# Thrusters_terminals_pcb.net
KiCad netlist of a schematic drawn in EAGLE
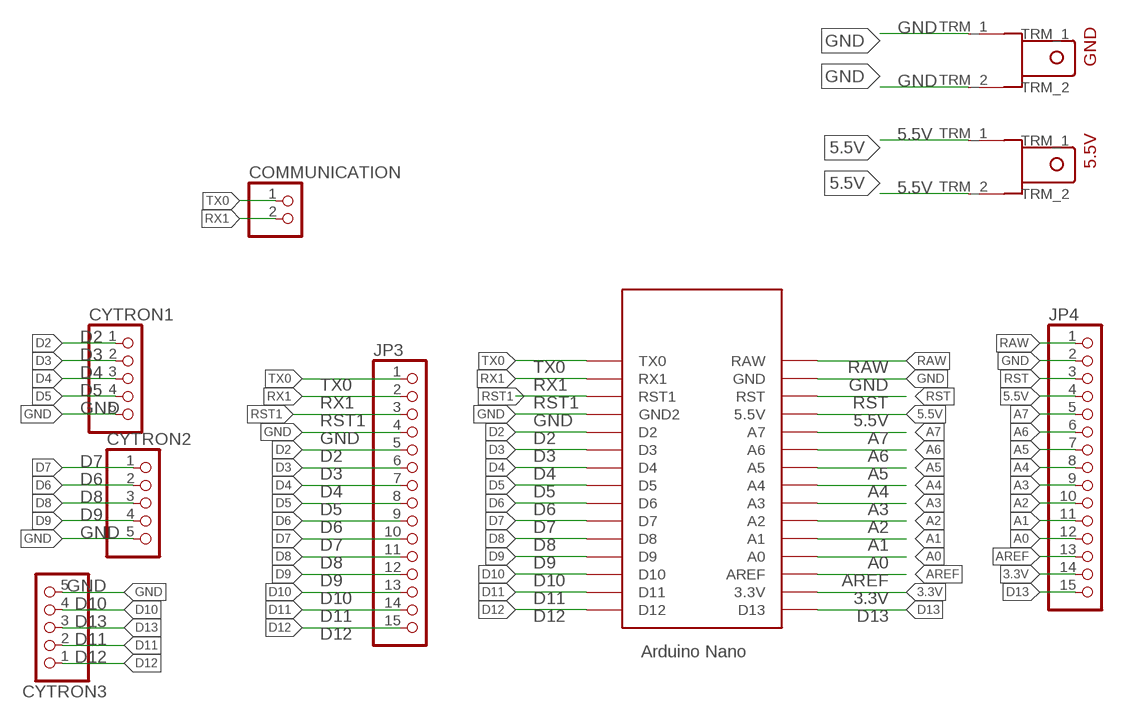
[diagram p0: schematic, sheet 1]

(export (version "E")
  (design (tool "Eeschema 10.0.6"))
  (components
    (comp (ref "5.5V")
      (value "TERMINAL_EDITED")
      (footprint "eagle-import:TERMINAL_EDITED")
      (libsource (lib "eagle-import") (part "TERMINAL_EDITED"))
    )
    (comp (ref "COMMUNICATION")
      (value "PINHD-2_DATA")
      (footprint "eagle-import:1X02_DATA")
      (libsource (lib "eagle-import") (part "PINHD-2_DATA"))
    )
    (comp (ref "CYTRON1")
      (value "PINHD-5_DATA")
      (footprint "eagle-import:1X05_DATA")
      (libsource (lib "eagle-import") (part "PINHD-5_DATA"))
    )
    (comp (ref "CYTRON2")
      (value "PINHD-5_DATA")
      (footprint "eagle-import:1X05_DATA")
      (libsource (lib "eagle-import") (part "PINHD-5_DATA"))
    )
    (comp (ref "CYTRON3")
      (value "PINHD-5_DATA")
      (footprint "eagle-import:1X05_DATA")
      (libsource (lib "eagle-import") (part "PINHD-5_DATA"))
    )
    (comp (ref "GND")
      (value "TERMINAL_EDITED")
      (footprint "eagle-import:TERMINAL_EDITED")
      (libsource (lib "eagle-import") (part "TERMINAL_EDITED"))
    )
    (comp (ref "JP3")
      (value "PINHD-1X15")
      (footprint "eagle-import:1X15")
      (libsource (lib "eagle-import") (part "PINHD-1X15"))
    )
    (comp (ref "JP4")
      (value "PINHD-1X15")
      (footprint "eagle-import:1X15")
      (libsource (lib "eagle-import") (part "PINHD-1X15"))
    )
    (comp (ref "U$1")
      (value "ARDUINO_NANO")
      (footprint "eagle-import:NANO")
      (libsource (lib "eagle-import") (part "ARDUINO_NANO"))
    )
  )
  (nets
    (net (code "1") (name "3.3V") (class "Default")
      (node (ref "JP4") (pin "14") (pinfunction "14_14") (pintype "passive"))
      (node (ref "U$1") (pin "3.3V") (pinfunction "3.3V_3.3V") (pintype "bidirectional"))
    )
    (net (code "2") (name "5.5V") (class "Default")
      (node (ref "5.5V") (pin "TRM_1") (pinfunction "TRM_1_TRM_1") (pintype "bidirectional"))
      (node (ref "5.5V") (pin "TRM_2") (pinfunction "TRM_2_TRM_2") (pintype "bidirectional"))
      (node (ref "JP4") (pin "4") (pinfunction "4_4") (pintype "passive"))
      (node (ref "U$1") (pin "5V") (pinfunction "5.5V_5V") (pintype "bidirectional"))
    )
    (net (code "3") (name "A0") (class "Default")
      (node (ref "JP4") (pin "12") (pinfunction "12_12") (pintype "passive"))
      (node (ref "U$1") (pin "A0") (pinfunction "A0_A0") (pintype "bidirectional"))
    )
    (net (code "4") (name "A1") (class "Default")
      (node (ref "JP4") (pin "11") (pinfunction "11_11") (pintype "passive"))
      (node (ref "U$1") (pin "A1") (pinfunction "A1_A1") (pintype "bidirectional"))
    )
    (net (code "5") (name "A2") (class "Default")
      (node (ref "JP4") (pin "10") (pinfunction "10_10") (pintype "passive"))
      (node (ref "U$1") (pin "A2") (pinfunction "A2_A2") (pintype "bidirectional"))
    )
    (net (code "6") (name "A3") (class "Default")
      (node (ref "JP4") (pin "9") (pinfunction "9_9") (pintype "passive"))
      (node (ref "U$1") (pin "A3") (pinfunction "A3_A3") (pintype "bidirectional"))
    )
    (net (code "7") (name "A4") (class "Default")
      (node (ref "JP4") (pin "8") (pinfunction "8_8") (pintype "passive"))
      (node (ref "U$1") (pin "A4") (pinfunction "A4_A4") (pintype "bidirectional"))
    )
    (net (code "8") (name "A5") (class "Default")
      (node (ref "JP4") (pin "7") (pinfunction "7_7") (pintype "passive"))
      (node (ref "U$1") (pin "A5") (pinfunction "A5_A5") (pintype "bidirectional"))
    )
    (net (code "9") (name "A6") (class "Default")
      (node (ref "JP4") (pin "6") (pinfunction "6_6") (pintype "passive"))
      (node (ref "U$1") (pin "A6") (pinfunction "A6_A6") (pintype "bidirectional"))
    )
    (net (code "10") (name "A7") (class "Default")
      (node (ref "JP4") (pin "5") (pinfunction "5_5") (pintype "passive"))
      (node (ref "U$1") (pin "A7") (pinfunction "A7_A7") (pintype "bidirectional"))
    )
    (net (code "11") (name "AREF") (class "Default")
      (node (ref "JP4") (pin "13") (pinfunction "13_13") (pintype "passive"))
      (node (ref "U$1") (pin "AREF") (pinfunction "AREF_AREF") (pintype "bidirectional"))
    )
    (net (code "12") (name "D2") (class "Default")
      (node (ref "CYTRON1") (pin "1") (pinfunction "1_1") (pintype "passive"))
      (node (ref "JP3") (pin "5") (pinfunction "5_5") (pintype "passive"))
      (node (ref "U$1") (pin "D2") (pinfunction "D2_D2") (pintype "bidirectional"))
    )
    (net (code "13") (name "D3") (class "Default")
      (node (ref "CYTRON1") (pin "2") (pinfunction "2_2") (pintype "passive"))
      (node (ref "JP3") (pin "6") (pinfunction "6_6") (pintype "passive"))
      (node (ref "U$1") (pin "D3") (pinfunction "D3_D3") (pintype "bidirectional"))
    )
    (net (code "14") (name "D4") (class "Default")
      (node (ref "CYTRON1") (pin "3") (pinfunction "3_3") (pintype "passive"))
      (node (ref "JP3") (pin "7") (pinfunction "7_7") (pintype "passive"))
      (node (ref "U$1") (pin "D4") (pinfunction "D4_D4") (pintype "bidirectional"))
    )
    (net (code "15") (name "D5") (class "Default")
      (node (ref "CYTRON1") (pin "4") (pinfunction "4_4") (pintype "passive"))
      (node (ref "JP3") (pin "8") (pinfunction "8_8") (pintype "passive"))
      (node (ref "U$1") (pin "D5") (pinfunction "D5_D5") (pintype "bidirectional"))
    )
    (net (code "16") (name "D6") (class "Default")
      (node (ref "CYTRON2") (pin "2") (pinfunction "2_2") (pintype "passive"))
      (node (ref "JP3") (pin "9") (pinfunction "9_9") (pintype "passive"))
      (node (ref "U$1") (pin "D6") (pinfunction "D6_D6") (pintype "bidirectional"))
    )
    (net (code "17") (name "D7") (class "Default")
      (node (ref "CYTRON2") (pin "1") (pinfunction "1_1") (pintype "passive"))
      (node (ref "JP3") (pin "10") (pinfunction "10_10") (pintype "passive"))
      (node (ref "U$1") (pin "D7") (pinfunction "D7_D7") (pintype "bidirectional"))
    )
    (net (code "18") (name "D8") (class "Default")
      (node (ref "CYTRON2") (pin "3") (pinfunction "3_3") (pintype "passive"))
      (node (ref "JP3") (pin "11") (pinfunction "11_11") (pintype "passive"))
      (node (ref "U$1") (pin "D8") (pinfunction "D8_D8") (pintype "bidirectional"))
    )
    (net (code "19") (name "D9") (class "Default")
      (node (ref "CYTRON2") (pin "4") (pinfunction "4_4") (pintype "passive"))
      (node (ref "JP3") (pin "12") (pinfunction "12_12") (pintype "passive"))
      (node (ref "U$1") (pin "D9") (pinfunction "D9_D9") (pintype "bidirectional"))
    )
    (net (code "20") (name "D10") (class "Default")
      (node (ref "CYTRON3") (pin "4") (pinfunction "4_4") (pintype "passive"))
      (node (ref "JP3") (pin "13") (pinfunction "13_13") (pintype "passive"))
      (node (ref "U$1") (pin "D10") (pinfunction "D10_D10") (pintype "bidirectional"))
    )
    (net (code "21") (name "D11") (class "Default")
      (node (ref "CYTRON3") (pin "2") (pinfunction "2_2") (pintype "passive"))
      (node (ref "JP3") (pin "14") (pinfunction "14_14") (pintype "passive"))
      (node (ref "U$1") (pin "D11") (pinfunction "D11_D11") (pintype "bidirectional"))
    )
    (net (code "22") (name "D12") (class "Default")
      (node (ref "CYTRON3") (pin "1") (pinfunction "1_1") (pintype "passive"))
      (node (ref "JP3") (pin "15") (pinfunction "15_15") (pintype "passive"))
      (node (ref "U$1") (pin "D12") (pinfunction "D12_D12") (pintype "bidirectional"))
    )
    (net (code "23") (name "D13") (class "Default")
      (node (ref "CYTRON3") (pin "3") (pinfunction "3_3") (pintype "passive"))
      (node (ref "JP4") (pin "15") (pinfunction "15_15") (pintype "passive"))
      (node (ref "U$1") (pin "D13") (pinfunction "D13_D13") (pintype "bidirectional"))
    )
    (net (code "24") (name "GND") (class "Default")
      (node (ref "CYTRON1") (pin "5") (pinfunction "5_5") (pintype "passive"))
      (node (ref "CYTRON2") (pin "5") (pinfunction "5_5") (pintype "passive"))
      (node (ref "CYTRON3") (pin "5") (pinfunction "5_5") (pintype "passive"))
      (node (ref "GND") (pin "TRM_1") (pinfunction "TRM_1_TRM_1") (pintype "bidirectional"))
      (node (ref "GND") (pin "TRM_2") (pinfunction "TRM_2_TRM_2") (pintype "bidirectional"))
      (node (ref "JP3") (pin "4") (pinfunction "4_4") (pintype "passive"))
      (node (ref "JP4") (pin "2") (pinfunction "2_2") (pintype "passive"))
      (node (ref "U$1") (pin "GND") (pinfunction "GND_GND") (pintype "bidirectional"))
      (node (ref "U$1") (pin "GND1") (pinfunction "GND2_GND1") (pintype "bidirectional"))
    )
    (net (code "25") (name "RAW") (class "Default")
      (node (ref "JP4") (pin "1") (pinfunction "1_1") (pintype "passive"))
      (node (ref "U$1") (pin "RAW") (pinfunction "RAW_RAW") (pintype "bidirectional"))
    )
    (net (code "26") (name "RST") (class "Default")
      (node (ref "JP4") (pin "3") (pinfunction "3_3") (pintype "passive"))
      (node (ref "U$1") (pin "RST") (pinfunction "RST_RST") (pintype "bidirectional"))
    )
    (net (code "27") (name "RST1") (class "Default")
      (node (ref "JP3") (pin "3") (pinfunction "3_3") (pintype "passive"))
      (node (ref "U$1") (pin "RST1") (pinfunction "RST1_RST1") (pintype "bidirectional"))
    )
    (net (code "28") (name "RX1") (class "Default")
      (node (ref "COMMUNICATION") (pin "2") (pinfunction "2_2") (pintype "passive"))
      (node (ref "JP3") (pin "2") (pinfunction "2_2") (pintype "passive"))
      (node (ref "U$1") (pin "RX1") (pinfunction "RX1_RX1") (pintype "bidirectional"))
    )
    (net (code "29") (name "TX0") (class "Default")
      (node (ref "COMMUNICATION") (pin "1") (pinfunction "1_1") (pintype "passive"))
      (node (ref "JP3") (pin "1") (pinfunction "1_1") (pintype "passive"))
      (node (ref "U$1") (pin "TX0") (pinfunction "TX0_TX0") (pintype "bidirectional"))
    )
  )
)
